# indicator.net
KiCad netlist of a schematic drawn in Altium Designer
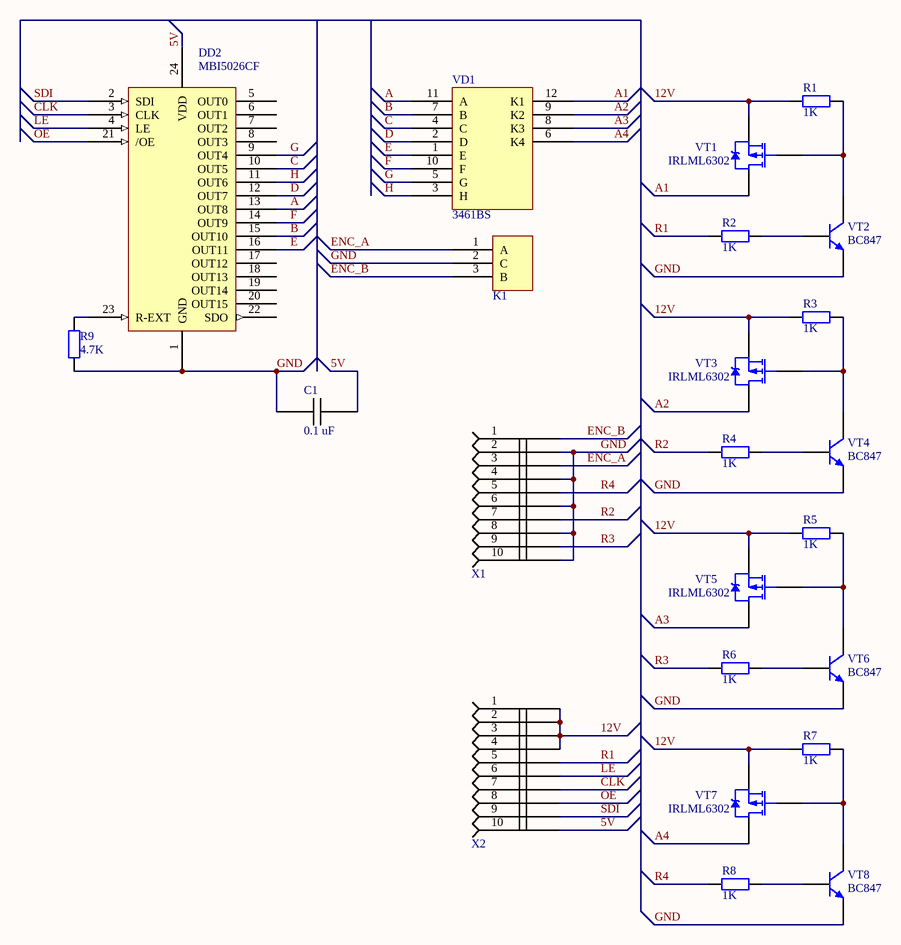
[diagram p0: indicator.SchDoc]

(export (version "E")
  (design (tool "Eeschema 10.0.6"))
  (components
    (comp (ref "C1") (value "0.1 uF") (footprint "R1206") (libsource (lib "Schlib1") (part "CAP_1206")))
    (comp (ref "DD2") (value "MBI5026CF") (footprint "SOP24") (libsource (lib "Schlib1") (part "MBI5026CF")))
    (comp (ref "K1")
      (value "EC12")
      (footprint "EC12E1220406")
      (libsource (lib "Schlib1") (part "EC12E1220406"))
    )
    (comp (ref "R1") (value "1K") (footprint "PcbLib1:R1206") (libsource (lib "Schlib1") (part "Res")))
    (comp (ref "R2") (value "1K") (footprint "PcbLib1:R1206") (libsource (lib "Schlib1") (part "Res")))
    (comp (ref "R3") (value "1K") (footprint "PcbLib1:R1206") (libsource (lib "Schlib1") (part "Res")))
    (comp (ref "R4") (value "1K") (footprint "PcbLib1:R1206") (libsource (lib "Schlib1") (part "Res")))
    (comp (ref "R5") (value "1K") (footprint "PcbLib1:R1206") (libsource (lib "Schlib1") (part "Res")))
    (comp (ref "R6") (value "1K") (footprint "PcbLib1:R1206") (libsource (lib "Schlib1") (part "Res")))
    (comp (ref "R7") (value "1K") (footprint "PcbLib1:R1206") (libsource (lib "Schlib1") (part "Res")))
    (comp (ref "R8") (value "1K") (footprint "PcbLib1:R1206") (libsource (lib "Schlib1") (part "Res")))
    (comp (ref "R9") (value "4.7K") (footprint "PcbLib1:R1206") (libsource (lib "") (part "Res_1")))
    (comp (ref "VD1") (value "3461BS") (footprint "3461bs") (libsource (lib "Schlib1") (part "3461BS")))
    (comp (ref "VT1")
      (value "IRLML6302")
      (footprint "SOT-23_N")
      (description "HEXFET Power MOSFET")
      (fields (field (name "PUBLISHER") "Altium Limited"))
      (libsource (lib "IR Discrete MOSFET - Power") (part "IRLML6302"))
    )
    (comp (ref "VT2")
      (value "BC847")
      (footprint "SOT23_N")
      (description "NPN General-purpose Transistor")
      (fields (field (name "PUBLISHER") "Altium Limited"))
      (libsource (lib "Philips Discrete BJT - Low Power") (part "BC847"))
    )
    (comp (ref "VT3")
      (value "IRLML6302")
      (footprint "SOT-23_N")
      (description "HEXFET Power MOSFET")
      (fields (field (name "PUBLISHER") "Altium Limited"))
      (libsource (lib "IR Discrete MOSFET - Power") (part "IRLML6302"))
    )
    (comp (ref "VT4")
      (value "BC847")
      (footprint "SOT23_N")
      (description "NPN General-purpose Transistor")
      (fields (field (name "PUBLISHER") "Altium Limited"))
      (libsource (lib "Philips Discrete BJT - Low Power") (part "BC847"))
    )
    (comp (ref "VT5")
      (value "IRLML6302")
      (footprint "SOT-23_N")
      (description "HEXFET Power MOSFET")
      (fields (field (name "PUBLISHER") "Altium Limited"))
      (libsource (lib "IR Discrete MOSFET - Power") (part "IRLML6302"))
    )
    (comp (ref "VT6")
      (value "BC847")
      (footprint "SOT23_N")
      (description "NPN General-purpose Transistor")
      (fields (field (name "PUBLISHER") "Altium Limited"))
      (libsource (lib "Philips Discrete BJT - Low Power") (part "BC847"))
    )
    (comp (ref "VT7")
      (value "IRLML6302")
      (footprint "SOT-23_N")
      (description "HEXFET Power MOSFET")
      (fields (field (name "PUBLISHER") "Altium Limited"))
      (libsource (lib "IR Discrete MOSFET - Power") (part "IRLML6302"))
    )
    (comp (ref "VT8")
      (value "BC847")
      (footprint "SOT23_N")
      (description "NPN General-purpose Transistor")
      (fields (field (name "PUBLISHER") "Altium Limited"))
      (libsource (lib "Philips Discrete BJT - Low Power") (part "BC847"))
    )
    (comp (ref "X1") (value "PBS-10") (footprint "PBS-10") (libsource (lib "Schlib1") (part "PBS-10")))
    (comp (ref "X2") (value "PBS-10") (footprint "PBS-10") (libsource (lib "Schlib1") (part "PBS-10")))
  )
  (nets
    (net (code "1") (name "/5V") (class "Default")
      (node (ref "C1") (pin "1") (pinfunction "1_1") (pintype "passive"))
      (node (ref "DD2") (pin "24") (pinfunction "VDD_24") (pintype "power_in"))
      (node (ref "X2") (pin "10") (pinfunction "10_10") (pintype "passive"))
    )
    (net (code "2") (name "/12V") (class "Default")
      (node (ref "R1") (pin "2") (pinfunction "2_2") (pintype "passive"))
      (node (ref "R3") (pin "2") (pinfunction "2_2") (pintype "passive"))
      (node (ref "R5") (pin "2") (pinfunction "2_2") (pintype "passive"))
      (node (ref "R7") (pin "2") (pinfunction "2_2") (pintype "passive"))
      (node (ref "VT1") (pin "2") (pinfunction "S_2") (pintype "passive"))
      (node (ref "VT3") (pin "2") (pinfunction "S_2") (pintype "passive"))
      (node (ref "VT5") (pin "2") (pinfunction "S_2") (pintype "passive"))
      (node (ref "VT7") (pin "2") (pinfunction "S_2") (pintype "passive"))
      (node (ref "X2") (pin "1") (pinfunction "1_1") (pintype "passive"))
      (node (ref "X2") (pin "2") (pinfunction "2_2") (pintype "passive"))
      (node (ref "X2") (pin "3") (pinfunction "3_3") (pintype "passive"))
      (node (ref "X2") (pin "4") (pinfunction "4_4") (pintype "passive"))
    )
    (net (code "3") (name "/A") (class "Default")
      (node (ref "DD2") (pin "13") (pinfunction "OUT8_13") (pintype "open_collector"))
      (node (ref "VD1") (pin "11") (pinfunction "A_11") (pintype "passive"))
    )
    (net (code "4") (name "/A1") (class "Default")
      (node (ref "VD1") (pin "12") (pinfunction "K1_12") (pintype "passive"))
      (node (ref "VT1") (pin "3") (pinfunction "D_3") (pintype "passive"))
    )
    (net (code "5") (name "/A2") (class "Default")
      (node (ref "VD1") (pin "9") (pinfunction "K2_9") (pintype "passive"))
      (node (ref "VT3") (pin "3") (pinfunction "D_3") (pintype "passive"))
    )
    (net (code "6") (name "/A3") (class "Default")
      (node (ref "VD1") (pin "8") (pinfunction "K3_8") (pintype "passive"))
      (node (ref "VT5") (pin "3") (pinfunction "D_3") (pintype "passive"))
    )
    (net (code "7") (name "/A4") (class "Default")
      (node (ref "VD1") (pin "6") (pinfunction "K4_6") (pintype "passive"))
      (node (ref "VT7") (pin "3") (pinfunction "D_3") (pintype "passive"))
    )
    (net (code "8") (name "/B") (class "Default")
      (node (ref "DD2") (pin "15") (pinfunction "OUT10_15") (pintype "open_collector"))
      (node (ref "VD1") (pin "7") (pinfunction "B_7") (pintype "passive"))
    )
    (net (code "9") (name "/C") (class "Default")
      (node (ref "DD2") (pin "10") (pinfunction "OUT5_10") (pintype "open_collector"))
      (node (ref "VD1") (pin "4") (pinfunction "C_4") (pintype "passive"))
    )
    (net (code "10") (name "/CLK") (class "Default")
      (node (ref "DD2") (pin "3") (pinfunction "CLK_3") (pintype "input"))
      (node (ref "X2") (pin "7") (pinfunction "7_7") (pintype "passive"))
    )
    (net (code "11") (name "/D") (class "Default")
      (node (ref "DD2") (pin "12") (pinfunction "OUT7_12") (pintype "open_collector"))
      (node (ref "VD1") (pin "2") (pinfunction "D_2") (pintype "passive"))
    )
    (net (code "12") (name "/E") (class "Default")
      (node (ref "DD2") (pin "16") (pinfunction "OUT11_16") (pintype "open_collector"))
      (node (ref "VD1") (pin "1") (pinfunction "E_1") (pintype "passive"))
    )
    (net (code "13") (name "/ENC_A") (class "Default")
      (node (ref "K1") (pin "1") (pinfunction "A_1") (pintype "passive"))
      (node (ref "X1") (pin "3") (pinfunction "3_3") (pintype "passive"))
    )
    (net (code "14") (name "/ENC_B") (class "Default")
      (node (ref "K1") (pin "3") (pinfunction "B_3") (pintype "passive"))
      (node (ref "X1") (pin "1") (pinfunction "1_1") (pintype "passive"))
    )
    (net (code "15") (name "/F") (class "Default")
      (node (ref "DD2") (pin "14") (pinfunction "OUT9_14") (pintype "open_collector"))
      (node (ref "VD1") (pin "10") (pinfunction "F_10") (pintype "passive"))
    )
    (net (code "16") (name "/G") (class "Default")
      (node (ref "DD2") (pin "9") (pinfunction "OUT4_9") (pintype "open_collector"))
      (node (ref "VD1") (pin "5") (pinfunction "G_5") (pintype "passive"))
    )
    (net (code "17") (name "/GND") (class "Default")
      (node (ref "C1") (pin "2") (pinfunction "2_2") (pintype "passive"))
      (node (ref "DD2") (pin "1") (pinfunction "GND_1") (pintype "power_in"))
      (node (ref "K1") (pin "2") (pinfunction "C_2") (pintype "passive"))
      (node (ref "R9") (pin "1") (pinfunction "1_1") (pintype "passive"))
      (node (ref "VT2") (pin "2") (pinfunction "E_2") (pintype "passive"))
      (node (ref "VT4") (pin "2") (pinfunction "E_2") (pintype "passive"))
      (node (ref "VT6") (pin "2") (pinfunction "E_2") (pintype "passive"))
      (node (ref "VT8") (pin "2") (pinfunction "E_2") (pintype "passive"))
      (node (ref "X1") (pin "10") (pinfunction "10_10") (pintype "passive"))
      (node (ref "X1") (pin "2") (pinfunction "2_2") (pintype "passive"))
      (node (ref "X1") (pin "4") (pinfunction "4_4") (pintype "passive"))
      (node (ref "X1") (pin "6") (pinfunction "6_6") (pintype "passive"))
      (node (ref "X1") (pin "8") (pinfunction "8_8") (pintype "passive"))
    )
    (net (code "18") (name "/H") (class "Default")
      (node (ref "DD2") (pin "11") (pinfunction "OUT6_11") (pintype "open_collector"))
      (node (ref "VD1") (pin "3") (pinfunction "H_3") (pintype "passive"))
    )
    (net (code "19") (name "/LE") (class "Default")
      (node (ref "DD2") (pin "4") (pinfunction "LE_4") (pintype "input"))
      (node (ref "X2") (pin "6") (pinfunction "6_6") (pintype "passive"))
    )
    (net (code "20") (name "/OE") (class "Default")
      (node (ref "DD2") (pin "21") (pinfunction "/OE_21") (pintype "input"))
      (node (ref "X2") (pin "8") (pinfunction "8_8") (pintype "passive"))
    )
    (net (code "21") (name "/R1") (class "Default")
      (node (ref "R2") (pin "2") (pinfunction "2_2") (pintype "passive"))
      (node (ref "X2") (pin "5") (pinfunction "5_5") (pintype "passive"))
    )
    (net (code "22") (name "/R2") (class "Default")
      (node (ref "R4") (pin "2") (pinfunction "2_2") (pintype "passive"))
      (node (ref "X1") (pin "7") (pinfunction "7_7") (pintype "passive"))
    )
    (net (code "23") (name "/R3") (class "Default")
      (node (ref "R6") (pin "2") (pinfunction "2_2") (pintype "passive"))
      (node (ref "X1") (pin "9") (pinfunction "9_9") (pintype "passive"))
    )
    (net (code "24") (name "/R4") (class "Default")
      (node (ref "R8") (pin "2") (pinfunction "2_2") (pintype "passive"))
      (node (ref "X1") (pin "5") (pinfunction "5_5") (pintype "passive"))
    )
    (net (code "25") (name "/SDI") (class "Default")
      (node (ref "DD2") (pin "2") (pinfunction "SDI_2") (pintype "input"))
      (node (ref "X2") (pin "9") (pinfunction "9_9") (pintype "passive"))
    )
    (net (code "26") (name "Net-(DD2-R-EXT)") (class "Default")
      (node (ref "DD2") (pin "23") (pinfunction "R-EXT_23") (pintype "input"))
      (node (ref "R9") (pin "2") (pinfunction "2_2") (pintype "passive"))
    )
    (net (code "27") (name "Net-(VT1-G)") (class "Default")
      (node (ref "R1") (pin "1") (pinfunction "1_1") (pintype "passive"))
      (node (ref "VT1") (pin "1") (pinfunction "G_1") (pintype "passive"))
      (node (ref "VT2") (pin "3") (pinfunction "C_3") (pintype "passive"))
    )
    (net (code "28") (name "Net-(VT2-B)") (class "Default")
      (node (ref "R2") (pin "1") (pinfunction "1_1") (pintype "passive"))
      (node (ref "VT2") (pin "1") (pinfunction "B_1") (pintype "passive"))
    )
    (net (code "29") (name "Net-(VT3-G)") (class "Default")
      (node (ref "R3") (pin "1") (pinfunction "1_1") (pintype "passive"))
      (node (ref "VT3") (pin "1") (pinfunction "G_1") (pintype "passive"))
      (node (ref "VT4") (pin "3") (pinfunction "C_3") (pintype "passive"))
    )
    (net (code "30") (name "Net-(VT4-B)") (class "Default")
      (node (ref "R4") (pin "1") (pinfunction "1_1") (pintype "passive"))
      (node (ref "VT4") (pin "1") (pinfunction "B_1") (pintype "passive"))
    )
    (net (code "31") (name "Net-(VT5-G)") (class "Default")
      (node (ref "R5") (pin "1") (pinfunction "1_1") (pintype "passive"))
      (node (ref "VT5") (pin "1") (pinfunction "G_1") (pintype "passive"))
      (node (ref "VT6") (pin "3") (pinfunction "C_3") (pintype "passive"))
    )
    (net (code "32") (name "Net-(VT6-B)") (class "Default")
      (node (ref "R6") (pin "1") (pinfunction "1_1") (pintype "passive"))
      (node (ref "VT6") (pin "1") (pinfunction "B_1") (pintype "passive"))
    )
    (net (code "33") (name "Net-(VT7-G)") (class "Default")
      (node (ref "R7") (pin "1") (pinfunction "1_1") (pintype "passive"))
      (node (ref "VT7") (pin "1") (pinfunction "G_1") (pintype "passive"))
      (node (ref "VT8") (pin "3") (pinfunction "C_3") (pintype "passive"))
    )
    (net (code "34") (name "Net-(VT8-B)") (class "Default")
      (node (ref "R8") (pin "1") (pinfunction "1_1") (pintype "passive"))
      (node (ref "VT8") (pin "1") (pinfunction "B_1") (pintype "passive"))
    )
    (net (code "35") (name "unconnected-(DD2-OUT0-Pad5)") (class "Default")
      (node (ref "DD2") (pin "5") (pinfunction "OUT0_5") (pintype "open_collector"))
    )
    (net (code "36") (name "unconnected-(DD2-OUT1-Pad6)") (class "Default")
      (node (ref "DD2") (pin "6") (pinfunction "OUT1_6") (pintype "open_collector"))
    )
    (net (code "37") (name "unconnected-(DD2-OUT2-Pad7)") (class "Default")
      (node (ref "DD2") (pin "7") (pinfunction "OUT2_7") (pintype "open_collector"))
    )
    (net (code "38") (name "unconnected-(DD2-OUT3-Pad8)") (class "Default")
      (node (ref "DD2") (pin "8") (pinfunction "OUT3_8") (pintype "open_collector"))
    )
    (net (code "39") (name "unconnected-(DD2-OUT12-Pad17)") (class "Default")
      (node (ref "DD2") (pin "17") (pinfunction "OUT12_17") (pintype "open_collector"))
    )
    (net (code "40") (name "unconnected-(DD2-OUT13-Pad18)") (class "Default")
      (node (ref "DD2") (pin "18") (pinfunction "OUT13_18") (pintype "open_collector"))
    )
    (net (code "41") (name "unconnected-(DD2-OUT14-Pad19)") (class "Default")
      (node (ref "DD2") (pin "19") (pinfunction "OUT14_19") (pintype "open_collector"))
    )
    (net (code "42") (name "unconnected-(DD2-OUT15-Pad20)") (class "Default")
      (node (ref "DD2") (pin "20") (pinfunction "OUT15_20") (pintype "open_collector"))
    )
    (net (code "43") (name "unconnected-(DD2-SDO-Pad22)") (class "Default")
      (node (ref "DD2") (pin "22") (pinfunction "SDO_22") (pintype "output"))
    )
  )
)
